# LEDclock_DCF77-RTC-BAT_2026-05-08.net
KiCad netlist of a schematic drawn in EasyEDA Pro
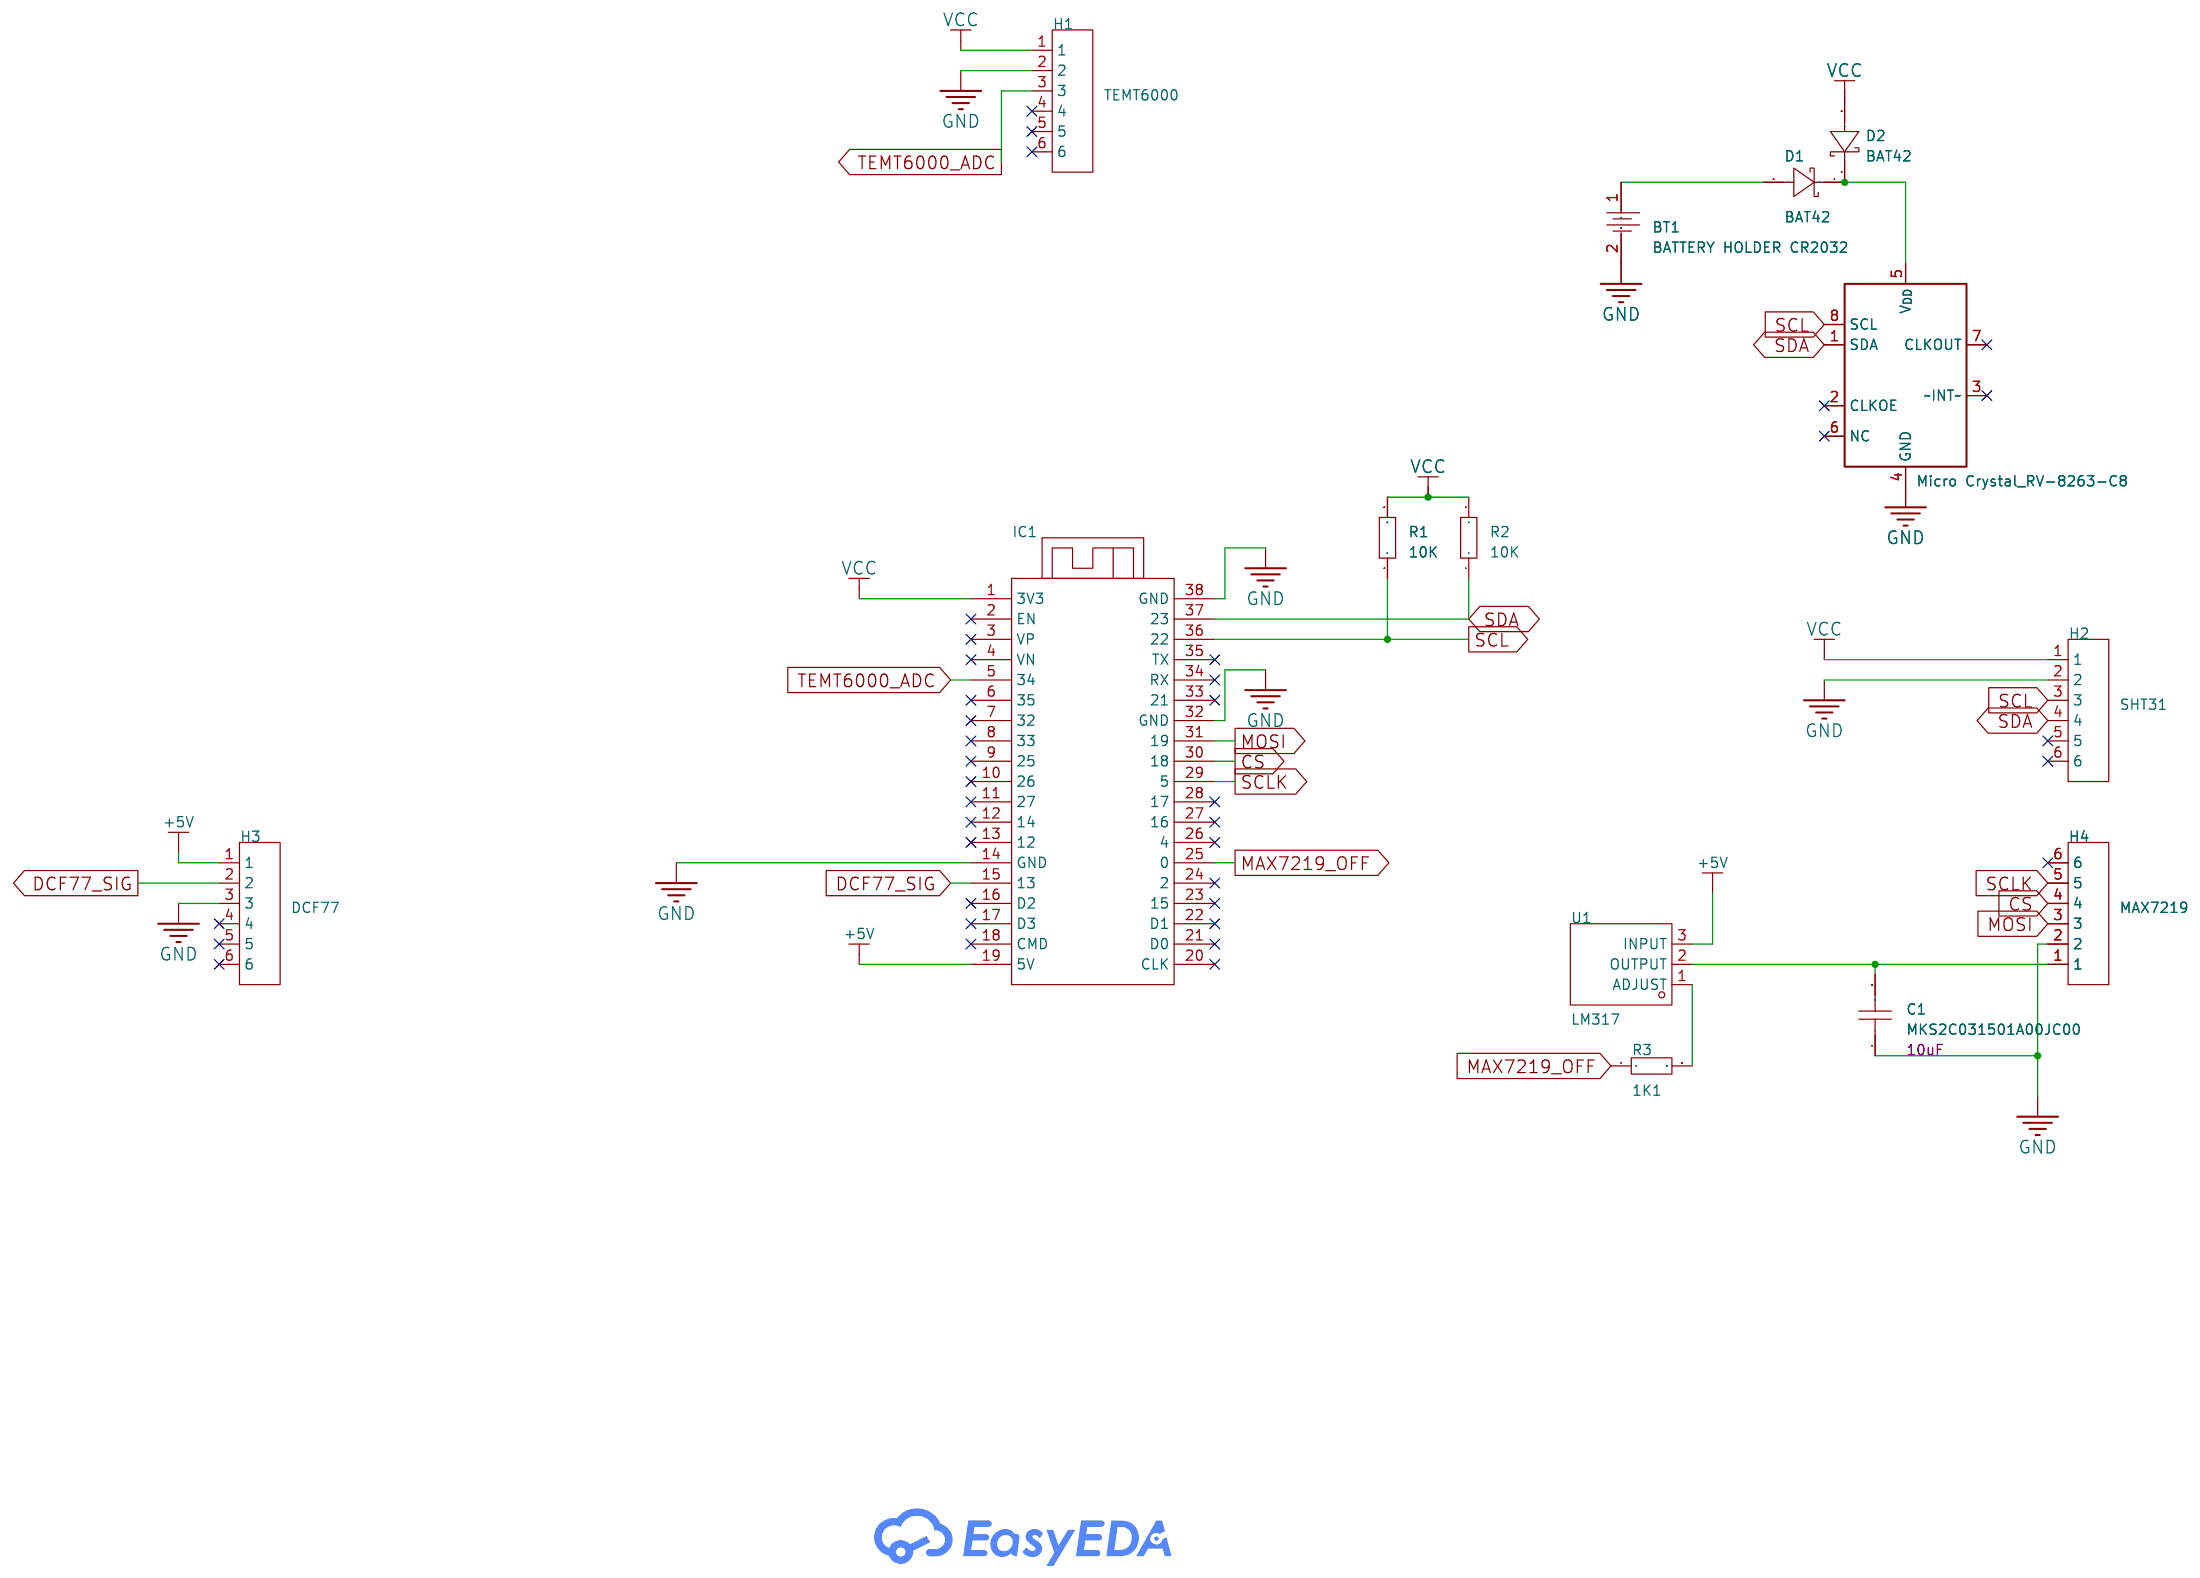
[diagram p0: schematic sheet]

(export (version "E")
  (design (tool "Eeschema 10.0.6"))
  (components
    (comp (ref "BT1")
      (value "BATTERY HOLDER CR2032")
      (footprint "easyedapro:BAT-TH_FBA25014-S02B2004K")
      (fields
        (field (name "Manufacturer Part") "FBA25014-S02B2004K")
        (field (name "Manufacturer") "TXGA(特思嘉)")
      )
      (libsource (lib "easyedapro") (part "FBA25014-S02B2004K"))
    )
    (comp (ref "C1")
      (value "MKS2C031501A00JC00")
      (footprint "easyedapro:CAP-TH_L7.2-W2.5-P5.00-D0.5-1")
      (fields (field (name "Manufacturer") "WIMA") (field (name "Capacitance") "10uF"))
      (libsource (lib "easyedapro") (part "MKS2C031501A00JC00"))
    )
    (comp (ref "D1")
      (value "BAT42")
      (footprint "easyedapro:DO-35_BD1.8-L4.1-P7.00-D0.5-RD")
      (fields (field (name "Manufacturer") "ST(意法半导体)"))
      (libsource (lib "easyedapro") (part "BAT42"))
    )
    (comp (ref "D2")
      (value "BAT42")
      (footprint "easyedapro:DO-35_BD1.8-L4.1-P7.00-D0.5-RD")
      (fields (field (name "Manufacturer") "ST(意法半导体)"))
      (libsource (lib "easyedapro") (part "BAT42"))
    )
    (comp (ref "H1")
      (value "TEMT6000")
      (footprint "easyedapro:CONN-TH_SSQ-106-03-G-S")
      (fields (field (name "Manufacturer") "SAMTEC"))
      (libsource (lib "easyedapro") (part "SSQ-106-03-G-S"))
    )
    (comp (ref "H2")
      (value "SHT31")
      (footprint "easyedapro:CONN-TH_SSQ-106-03-G-S")
      (fields (field (name "Manufacturer") "SAMTEC"))
      (libsource (lib "easyedapro") (part "SSQ-106-03-G-S"))
    )
    (comp (ref "H3")
      (value "DCF77")
      (footprint "easyedapro:CONN-TH_SSQ-106-03-G-S")
      (fields (field (name "Manufacturer") "SAMTEC"))
      (libsource (lib "easyedapro") (part "SSQ-106-03-G-S"))
    )
    (comp (ref "H4")
      (value "MAX7219")
      (footprint "easyedapro:CONN-TH_SSQ-106-03-G-S")
      (fields (field (name "Manufacturer") "SAMTEC"))
      (libsource (lib "easyedapro") (part "SSQ-106-03-G-S"))
    )
    (comp (ref "IC1")
      (value "~")
      (footprint "easyedapro:ESP32 WROOM devkit")
      (libsource (lib "easyedapro") (part "ESP32 WROOM defkit"))
    )
    (comp (ref "IC2")
      (value "RV-8263-C8")
      (footprint "easyedapro:Micro Crystal:RV-8263-C8")
      (libsource (lib "easyedapro") (part "Micro Crystal_RV-8263-C8"))
    )
    (comp (ref "R1") (value "10K") (footprint "easyedapro:R0603") (libsource (lib "easyedapro") (part "Res")))
    (comp (ref "R2") (value "10K") (footprint "easyedapro:R0603") (libsource (lib "easyedapro") (part "Res")))
    (comp (ref "R3") (value "1K1") (footprint "easyedapro:R0603") (libsource (lib "easyedapro") (part "Res")))
    (comp (ref "U1")
      (value "LM317")
      (footprint "easyedapro:TO-220-3_L9.9-W4.5-P2.54-L-1")
      (fields (field (name "Manufacturer") "IDCHIP(英锐芯)"))
      (libsource (lib "easyedapro") (part "LM317_C7463411"))
    )
  )
  (nets
    (net (code "1") (name "+5V") (class "Default")
      (node (ref "H3") (pin "1") (pinfunction "1_1") (pintype "unspecified"))
      (node (ref "IC1") (pin "19") (pinfunction "5V_19") (pintype "input"))
      (node (ref "U1") (pin "3") (pinfunction "INPUT_3") (pintype "unspecified"))
    )
    (net (code "2") (name "CS") (class "Default")
      (node (ref "H4") (pin "4") (pinfunction "4_4") (pintype "unspecified"))
      (node (ref "IC1") (pin "30") (pinfunction "18_30") (pintype "input"))
    )
    (net (code "3") (name "DCF77_SIG") (class "Default")
      (node (ref "H3") (pin "2") (pinfunction "2_2") (pintype "unspecified"))
      (node (ref "IC1") (pin "15") (pinfunction "13_15") (pintype "input"))
    )
    (net (code "4") (name "GND") (class "Default")
      (node (ref "BT1") (pin "2") (pinfunction "2_2") (pintype "input"))
      (node (ref "C1") (pin "1") (pinfunction "1_1") (pintype "unspecified"))
      (node (ref "H1") (pin "2") (pinfunction "2_2") (pintype "unspecified"))
      (node (ref "H2") (pin "2") (pinfunction "2_2") (pintype "unspecified"))
      (node (ref "H3") (pin "3") (pinfunction "3_3") (pintype "unspecified"))
      (node (ref "H4") (pin "2") (pinfunction "2_2") (pintype "unspecified"))
      (node (ref "IC1") (pin "14") (pinfunction "GND_14") (pintype "input"))
      (node (ref "IC1") (pin "32") (pinfunction "GND_32") (pintype "input"))
      (node (ref "IC1") (pin "38") (pinfunction "GND_38") (pintype "input"))
      (node (ref "IC2") (pin "4") (pinfunction "GND_4") (pintype "unspecified"))
    )
    (net (code "5") (name "MAX7219_OFF") (class "Default")
      (node (ref "IC1") (pin "25") (pinfunction "0_25") (pintype "input"))
      (node (ref "R3") (pin "1") (pinfunction "1_1") (pintype "input"))
    )
    (net (code "6") (name "MOSI") (class "Default")
      (node (ref "H4") (pin "3") (pinfunction "3_3") (pintype "unspecified"))
      (node (ref "IC1") (pin "31") (pinfunction "19_31") (pintype "input"))
    )
    (net (code "7") (name "Net-(D1-A)") (class "Default")
      (node (ref "BT1") (pin "1") (pinfunction "1_1") (pintype "input"))
      (node (ref "D1") (pin "2") (pinfunction "A_2") (pintype "unspecified"))
    )
    (net (code "8") (name "Net-(D1-K)") (class "Default")
      (node (ref "D1") (pin "1") (pinfunction "K_1") (pintype "unspecified"))
      (node (ref "D2") (pin "1") (pinfunction "K_1") (pintype "unspecified"))
      (node (ref "IC2") (pin "5") (pinfunction "V_{DD}_5") (pintype "unspecified"))
    )
    (net (code "9") (name "Net-(U1-ADJUST)") (class "Default")
      (node (ref "R3") (pin "2") (pinfunction "2_2") (pintype "input"))
      (node (ref "U1") (pin "1") (pinfunction "ADJUST_1") (pintype "unspecified"))
    )
    (net (code "10") (name "Net-(U1-OUTPUT)") (class "Default")
      (node (ref "C1") (pin "2") (pinfunction "2_2") (pintype "unspecified"))
      (node (ref "H4") (pin "1") (pinfunction "1_1") (pintype "unspecified"))
      (node (ref "U1") (pin "2") (pinfunction "OUTPUT_2") (pintype "unspecified"))
    )
    (net (code "11") (name "SCL") (class "Default")
      (node (ref "H2") (pin "3") (pinfunction "3_3") (pintype "unspecified"))
      (node (ref "IC1") (pin "36") (pinfunction "22_36") (pintype "input"))
      (node (ref "IC2") (pin "8") (pinfunction "SCL_8") (pintype "input"))
      (node (ref "R1") (pin "1") (pinfunction "1_1") (pintype "input"))
    )
    (net (code "12") (name "SCLK") (class "Default")
      (node (ref "H4") (pin "5") (pinfunction "5_5") (pintype "unspecified"))
      (node (ref "IC1") (pin "29") (pinfunction "5_29") (pintype "input"))
    )
    (net (code "13") (name "SDA") (class "Default")
      (node (ref "H2") (pin "4") (pinfunction "4_4") (pintype "unspecified"))
      (node (ref "IC1") (pin "37") (pinfunction "23_37") (pintype "input"))
      (node (ref "IC2") (pin "1") (pinfunction "SDA_1") (pintype "bidirectional"))
      (node (ref "R2") (pin "1") (pinfunction "1_1") (pintype "input"))
    )
    (net (code "14") (name "TEMT6000_ADC") (class "Default")
      (node (ref "H1") (pin "3") (pinfunction "3_3") (pintype "unspecified"))
      (node (ref "IC1") (pin "5") (pinfunction "34_5") (pintype "input"))
    )
    (net (code "15") (name "VCC") (class "Default")
      (node (ref "D2") (pin "2") (pinfunction "A_2") (pintype "unspecified"))
      (node (ref "H1") (pin "1") (pinfunction "1_1") (pintype "unspecified"))
      (node (ref "H2") (pin "1") (pinfunction "1_1") (pintype "unspecified"))
      (node (ref "IC1") (pin "1") (pinfunction "3V3_1") (pintype "input"))
      (node (ref "R1") (pin "2") (pinfunction "2_2") (pintype "input"))
      (node (ref "R2") (pin "2") (pinfunction "2_2") (pintype "input"))
    )
    (net (code "16") (name "unconnected-(H1-Pad4)") (class "Default")
      (node (ref "H1") (pin "4") (pinfunction "4_4") (pintype "unspecified+no_connect"))
    )
    (net (code "17") (name "unconnected-(H1-Pad5)") (class "Default")
      (node (ref "H1") (pin "5") (pinfunction "5_5") (pintype "unspecified+no_connect"))
    )
    (net (code "18") (name "unconnected-(H1-Pad6)") (class "Default")
      (node (ref "H1") (pin "6") (pinfunction "6_6") (pintype "unspecified+no_connect"))
    )
    (net (code "19") (name "unconnected-(H2-Pad5)") (class "Default")
      (node (ref "H2") (pin "5") (pinfunction "5_5") (pintype "unspecified+no_connect"))
    )
    (net (code "20") (name "unconnected-(H2-Pad6)") (class "Default")
      (node (ref "H2") (pin "6") (pinfunction "6_6") (pintype "unspecified+no_connect"))
    )
    (net (code "21") (name "unconnected-(H3-Pad4)") (class "Default")
      (node (ref "H3") (pin "4") (pinfunction "4_4") (pintype "unspecified+no_connect"))
    )
    (net (code "22") (name "unconnected-(H3-Pad5)") (class "Default")
      (node (ref "H3") (pin "5") (pinfunction "5_5") (pintype "unspecified+no_connect"))
    )
    (net (code "23") (name "unconnected-(H3-Pad6)") (class "Default")
      (node (ref "H3") (pin "6") (pinfunction "6_6") (pintype "unspecified+no_connect"))
    )
    (net (code "24") (name "unconnected-(H4-Pad6)") (class "Default")
      (node (ref "H4") (pin "6") (pinfunction "6_6") (pintype "unspecified+no_connect"))
    )
    (net (code "25") (name "unconnected-(IC1-2-Pad24)") (class "Default")
      (node (ref "IC1") (pin "24") (pinfunction "2_24") (pintype "input+no_connect"))
    )
    (net (code "26") (name "unconnected-(IC1-4-Pad26)") (class "Default")
      (node (ref "IC1") (pin "26") (pinfunction "4_26") (pintype "input+no_connect"))
    )
    (net (code "27") (name "unconnected-(IC1-12-Pad13)") (class "Default")
      (node (ref "IC1") (pin "13") (pinfunction "12_13") (pintype "input+no_connect"))
    )
    (net (code "28") (name "unconnected-(IC1-14-Pad12)") (class "Default")
      (node (ref "IC1") (pin "12") (pinfunction "14_12") (pintype "input+no_connect"))
    )
    (net (code "29") (name "unconnected-(IC1-15-Pad23)") (class "Default")
      (node (ref "IC1") (pin "23") (pinfunction "15_23") (pintype "input+no_connect"))
    )
    (net (code "30") (name "unconnected-(IC1-16-Pad27)") (class "Default")
      (node (ref "IC1") (pin "27") (pinfunction "16_27") (pintype "input+no_connect"))
    )
    (net (code "31") (name "unconnected-(IC1-17-Pad28)") (class "Default")
      (node (ref "IC1") (pin "28") (pinfunction "17_28") (pintype "input+no_connect"))
    )
    (net (code "32") (name "unconnected-(IC1-21-Pad33)") (class "Default")
      (node (ref "IC1") (pin "33") (pinfunction "21_33") (pintype "input+no_connect"))
    )
    (net (code "33") (name "unconnected-(IC1-25-Pad9)") (class "Default")
      (node (ref "IC1") (pin "9") (pinfunction "25_9") (pintype "input+no_connect"))
    )
    (net (code "34") (name "unconnected-(IC1-26-Pad10)") (class "Default")
      (node (ref "IC1") (pin "10") (pinfunction "26_10") (pintype "input+no_connect"))
    )
    (net (code "35") (name "unconnected-(IC1-27-Pad11)") (class "Default")
      (node (ref "IC1") (pin "11") (pinfunction "27_11") (pintype "input+no_connect"))
    )
    (net (code "36") (name "unconnected-(IC1-32-Pad7)") (class "Default")
      (node (ref "IC1") (pin "7") (pinfunction "32_7") (pintype "input+no_connect"))
    )
    (net (code "37") (name "unconnected-(IC1-33-Pad8)") (class "Default")
      (node (ref "IC1") (pin "8") (pinfunction "33_8") (pintype "input+no_connect"))
    )
    (net (code "38") (name "unconnected-(IC1-35-Pad6)") (class "Default")
      (node (ref "IC1") (pin "6") (pinfunction "35_6") (pintype "input+no_connect"))
    )
    (net (code "39") (name "unconnected-(IC1-CLK-Pad20)") (class "Default")
      (node (ref "IC1") (pin "20") (pinfunction "CLK_20") (pintype "input+no_connect"))
    )
    (net (code "40") (name "unconnected-(IC1-CMD-Pad18)") (class "Default")
      (node (ref "IC1") (pin "18") (pinfunction "CMD_18") (pintype "input+no_connect"))
    )
    (net (code "41") (name "unconnected-(IC1-D0-Pad21)") (class "Default")
      (node (ref "IC1") (pin "21") (pinfunction "D0_21") (pintype "input+no_connect"))
    )
    (net (code "42") (name "unconnected-(IC1-D1-Pad22)") (class "Default")
      (node (ref "IC1") (pin "22") (pinfunction "D1_22") (pintype "input+no_connect"))
    )
    (net (code "43") (name "unconnected-(IC1-D2-Pad16)") (class "Default")
      (node (ref "IC1") (pin "16") (pinfunction "D2_16") (pintype "input+no_connect"))
    )
    (net (code "44") (name "unconnected-(IC1-D3-Pad17)") (class "Default")
      (node (ref "IC1") (pin "17") (pinfunction "D3_17") (pintype "input+no_connect"))
    )
    (net (code "45") (name "unconnected-(IC1-EN-Pad2)") (class "Default")
      (node (ref "IC1") (pin "2") (pinfunction "EN_2") (pintype "input+no_connect"))
    )
    (net (code "46") (name "unconnected-(IC1-RX-Pad34)") (class "Default")
      (node (ref "IC1") (pin "34") (pinfunction "RX_34") (pintype "input+no_connect"))
    )
    (net (code "47") (name "unconnected-(IC1-TX-Pad35)") (class "Default")
      (node (ref "IC1") (pin "35") (pinfunction "TX_35") (pintype "input+no_connect"))
    )
    (net (code "48") (name "unconnected-(IC1-VN-Pad4)") (class "Default")
      (node (ref "IC1") (pin "4") (pinfunction "VN_4") (pintype "input+no_connect"))
    )
    (net (code "49") (name "unconnected-(IC1-VP-Pad3)") (class "Default")
      (node (ref "IC1") (pin "3") (pinfunction "VP_3") (pintype "input+no_connect"))
    )
    (net (code "50") (name "unconnected-(IC2-CLKOE-Pad2)") (class "Default")
      (node (ref "IC2") (pin "2") (pinfunction "CLKOE_2") (pintype "input+no_connect"))
    )
    (net (code "51") (name "unconnected-(IC2-CLKOUT-Pad7)") (class "Default")
      (node (ref "IC2") (pin "7") (pinfunction "CLKOUT_7") (pintype "output+no_connect"))
    )
    (net (code "52") (name "unconnected-(IC2-NC-Pad6)") (class "Default")
      (node (ref "IC2") (pin "6") (pinfunction "NC_6") (pintype "unspecified+no_connect"))
    )
    (net (code "53") (name "unconnected-(IC2-~INT~-Pad3)") (class "Default")
      (node (ref "IC2") (pin "3") (pinfunction "~INT~_3") (pintype "output+no_connect"))
    )
  )
)
